# WalkMod_C0.net
KiCad netlist of a schematic drawn in Altium Designer
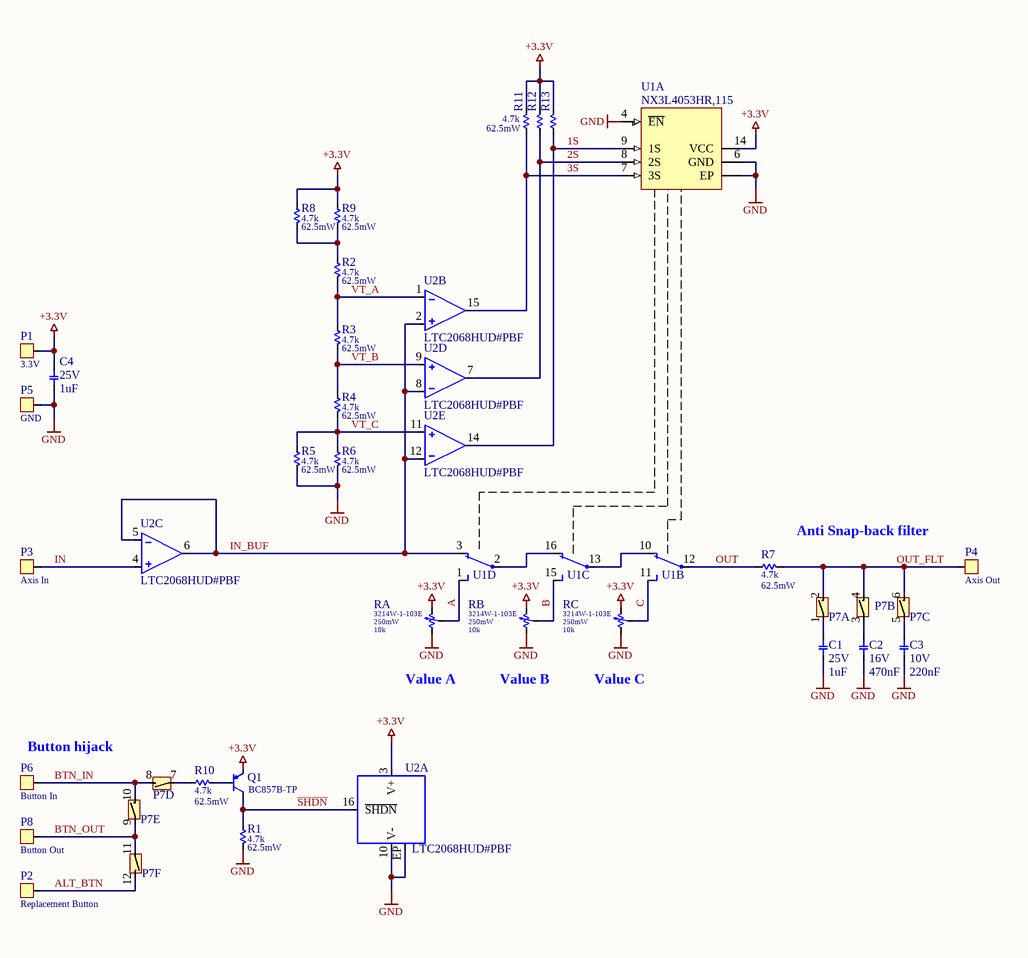
[diagram p0: WalkMod C0.SchDoc]

(export (version "E")
  (design (tool "Eeschema 10.0.6"))
  (components
    (comp (ref "C1")
      (value "1uF")
      (footprint "CX7R0603K")
      (description "1 µF ±10% 25V Ceramic Capacitor X7R 0603 (1608 Metric)")
      (fields (field (name "VALUE2") "25V") (field (name "Comment") "CL10B105KA8NFNC"))
      (libsource (lib "WalkMod") (part "kyocera-C-X7R-0603"))
    )
    (comp (ref "C2")
      (value "470nF")
      (footprint "CX7R0603K")
      (description "0.47 µF ±10% 16V Ceramic Capacitor X7R 0603 (1608 Metric)")
      (fields (field (name "VALUE2") "16V") (field (name "Comment") "CL10B474KO8NFNC"))
      (libsource (lib "WalkMod") (part "kyocera-C-X7R-0603"))
    )
    (comp (ref "C3")
      (value "220nF")
      (footprint "CX7R0603K")
      (description "0.22 µF ±10% 10V Ceramic Capacitor X7R 0603 (1608 Metric)")
      (fields (field (name "VALUE2") "10V") (field (name "Comment") "CC0603KRX7R6BB224"))
      (libsource (lib "WalkMod") (part "kyocera-C-X7R-0603"))
    )
    (comp (ref "C4")
      (value "1uF")
      (footprint "CX7R0603K")
      (description "1 µF ±10% 25V Ceramic Capacitor X7R 0603 (1608 Metric)")
      (fields (field (name "VALUE2") "25V") (field (name "Comment") "CL10B105KA8NFNC"))
      (libsource (lib "WalkMod") (part "kyocera-C-X7R-0603"))
    )
    (comp (ref "P1")
      (value "SMD Pad 1 pin")
      (footprint "PAD_2X1.5_SQUARE")
      (description "Single SMD Pad")
      (fields (field (name "NAME") "3.3V"))
      (libsource (lib "WalkMod") (part "SMD Pad 1 pin"))
    )
    (comp (ref "P2")
      (value "SMD Pad 1 pin")
      (footprint "PAD_2X1.5_SQUARE")
      (description "Single SMD Pad")
      (fields (field (name "NAME") "Replacement Button"))
      (libsource (lib "WalkMod") (part "SMD Pad 1 pin"))
    )
    (comp (ref "P3")
      (value "SMD Pad 1 pin")
      (footprint "PAD_2X1.5_SQUARE")
      (description "Single SMD Pad")
      (fields (field (name "NAME") "Axis In"))
      (libsource (lib "WalkMod") (part "SMD Pad 1 pin"))
    )
    (comp (ref "P4")
      (value "SMD Pad 1 pin")
      (footprint "PAD_2X1.5_SQUARE")
      (description "Single SMD Pad")
      (fields (field (name "NAME") "Axis Out"))
      (libsource (lib "") (part "SMD Pad 1 pin_1"))
    )
    (comp (ref "P5")
      (value "SMD Pad 1 pin")
      (footprint "PAD_2X1.5_SQUARE")
      (description "Single SMD Pad")
      (fields (field (name "NAME") "GND"))
      (libsource (lib "WalkMod") (part "SMD Pad 1 pin"))
    )
    (comp (ref "P6")
      (value "SMD Pad 1 pin")
      (footprint "PAD_2X1.5_SQUARE")
      (description "Single SMD Pad")
      (fields (field (name "NAME") "Button In"))
      (libsource (lib "WalkMod") (part "SMD Pad 1 pin"))
    )
    (comp (ref "P7")
      (value "DS05-127-2-06BK-SMT-TR")
      (footprint "CUI-DS05-127-2-06BK-SMT_C")
      (description "Dip Switch SPST 6 Position Surface Mount Slide (Standard) Actuator 25mA 24VDC")
      (libsource (lib "WalkMod") (part "DS05-127-2-06BK-SMT-TR"))
    )
    (comp (ref "P8")
      (value "SMD Pad 1 pin")
      (footprint "PAD_2X1.5_SQUARE")
      (description "Single SMD Pad")
      (fields (field (name "NAME") "Button Out"))
      (libsource (lib "WalkMod") (part "SMD Pad 1 pin"))
    )
    (comp (ref "Q1")
      (value "BC857B-TP")
      (footprint "BC8xx_SOT23-3_C")
      (description "Bipolar (BJT) Transistor PNP 45 V 100 mA 200MHz 310 mW Surface Mount SOT-23")
      (libsource (lib "WalkMod") (part "BC857B-TP"))
    )
    (comp (ref "R1")
      (value "4.7k")
      (footprint "RT0402_C")
      (fields (field (name "VALUE2") "62.5mW") (field (name "Comment") "RG1005P-472-B-T5"))
      (libsource (lib "WalkMod") (part "RT0402DRD0747KL"))
    )
    (comp (ref "R2")
      (value "4.7k")
      (footprint "RT0402_C")
      (fields (field (name "VALUE2") "62.5mW") (field (name "Comment") "RG1005P-472-B-T5"))
      (libsource (lib "WalkMod") (part "RT0402DRD0747KL"))
    )
    (comp (ref "R3")
      (value "4.7k")
      (footprint "RT0402_C")
      (fields (field (name "VALUE2") "62.5mW") (field (name "Comment") "RG1005P-472-B-T5"))
      (libsource (lib "WalkMod") (part "RT0402DRD0747KL"))
    )
    (comp (ref "R4")
      (value "4.7k")
      (footprint "RT0402_C")
      (fields (field (name "VALUE2") "62.5mW") (field (name "Comment") "RG1005P-472-B-T5"))
      (libsource (lib "WalkMod") (part "RT0402DRD0747KL"))
    )
    (comp (ref "R5")
      (value "4.7k")
      (footprint "RT0402_C")
      (fields (field (name "VALUE2") "62.5mW") (field (name "Comment") "RG1005P-472-B-T5"))
      (libsource (lib "WalkMod") (part "RT0402DRD0747KL"))
    )
    (comp (ref "R6")
      (value "4.7k")
      (footprint "RT0402_C")
      (fields (field (name "VALUE2") "62.5mW") (field (name "Comment") "RG1005P-472-B-T5"))
      (libsource (lib "WalkMod") (part "RT0402DRD0747KL"))
    )
    (comp (ref "R7")
      (value "4.7k")
      (footprint "RT0402_C")
      (fields (field (name "VALUE2") "62.5mW") (field (name "Comment") "RG1005P-472-B-T5"))
      (libsource (lib "WalkMod") (part "RT0402DRD0747KL"))
    )
    (comp (ref "R8")
      (value "4.7k")
      (footprint "RT0402_C")
      (fields (field (name "VALUE2") "62.5mW") (field (name "Comment") "RG1005P-472-B-T5"))
      (libsource (lib "WalkMod") (part "RT0402DRD0747KL"))
    )
    (comp (ref "R9")
      (value "4.7k")
      (footprint "RT0402_C")
      (fields (field (name "VALUE2") "62.5mW") (field (name "Comment") "RG1005P-472-B-T5"))
      (libsource (lib "WalkMod") (part "RT0402DRD0747KL"))
    )
    (comp (ref "R10")
      (value "4.7k")
      (footprint "RT0402_C")
      (fields (field (name "VALUE2") "62.5mW") (field (name "Comment") "RG1005P-472-B-T5"))
      (libsource (lib "WalkMod") (part "RT0402DRD0747KL"))
    )
    (comp (ref "R11")
      (value "4.7k")
      (footprint "RT0402_C")
      (fields (field (name "VALUE2") "62.5mW") (field (name "Comment") "RG1005P-472-B-T5"))
      (libsource (lib "WalkMod") (part "RT0402DRD0747KL"))
    )
    (comp (ref "R12")
      (value "RG1005P-472-B-T5")
      (footprint "RT0402_C")
      (libsource (lib "WalkMod") (part "RT0402DRD0747KL"))
    )
    (comp (ref "R13")
      (value "RG1005P-472-B-T5")
      (footprint "RT0402_C")
      (libsource (lib "WalkMod") (part "RT0402DRD0747KL"))
    )
    (comp (ref "RA")
      (value "3214W-1-103E")
      (footprint "BOURNS_3214W_C")
      (description "10 kOhms 0.25W, 1/4W J Lead Surface Mount Trimmer Potentiometer Cermet 5.0 Turn Top Adjustment")
      (fields (field (name "VALUE2") "250mW") (field (name "ALTIUM_VALUE") "10k"))
      (libsource (lib "WalkMod") (part "3214W-1-103E"))
    )
    (comp (ref "RB")
      (value "3214W-1-103E")
      (footprint "BOURNS_3214W_C")
      (description "10 kOhms 0.25W, 1/4W J Lead Surface Mount Trimmer Potentiometer Cermet 5.0 Turn Top Adjustment")
      (fields (field (name "VALUE2") "250mW") (field (name "ALTIUM_VALUE") "10k"))
      (libsource (lib "WalkMod") (part "3214W-1-103E"))
    )
    (comp (ref "RC")
      (value "3214W-1-103E")
      (footprint "BOURNS_3214W_C")
      (description "10 kOhms 0.25W, 1/4W J Lead Surface Mount Trimmer Potentiometer Cermet 5.0 Turn Top Adjustment")
      (fields (field (name "VALUE2") "250mW") (field (name "ALTIUM_VALUE") "10k"))
      (libsource (lib "WalkMod") (part "3214W-1-103E"))
    )
    (comp (ref "U1")
      (value "NX3L4053HR,115")
      (footprint "HXQFN16_SOT1039-2_C")
      (description "3 Circuit IC Switch 2:1 800mOhm 16-HXQFN (3x3)")
      (libsource (lib "") (part "NX3L4053_3"))
    )
    (comp (ref "U2")
      (value "LTC2068HUD#PBF")
      (footprint "QFN16_0.5_C")
      (description "Zero-Drift Amplifier 4 Circuit Rail-to-Rail 16-QFN (3x3)")
      (libsource (lib "WalkMod") (part "LTC2068HUD#PBF"))
    )
  )
  (nets
    (net (code "1") (name "+3.3V") (class "Default")
      (node (ref "C4") (pin "2") (pinfunction "2_2") (pintype "passive"))
      (node (ref "P1") (pin "1") (pinfunction "1_1") (pintype "passive"))
      (node (ref "Q1") (pin "E") (pinfunction "E_E") (pintype "passive"))
      (node (ref "R11") (pin "1") (pinfunction "1_1") (pintype "passive"))
      (node (ref "R12") (pin "1") (pinfunction "1_1") (pintype "passive"))
      (node (ref "R13") (pin "1") (pinfunction "1_1") (pintype "passive"))
      (node (ref "R8") (pin "2") (pinfunction "2_2") (pintype "passive"))
      (node (ref "R9") (pin "2") (pinfunction "2_2") (pintype "passive"))
      (node (ref "RA") (pin "3") (pinfunction "3_3") (pintype "passive"))
      (node (ref "RB") (pin "3") (pinfunction "3_3") (pintype "passive"))
      (node (ref "RC") (pin "3") (pinfunction "3_3") (pintype "passive"))
      (node (ref "U1") (pin "14") (pinfunction "VCC_14") (pintype "power_in"))
      (node (ref "U2") (pin "3") (pinfunction "V+_3") (pintype "passive"))
    )
    (net (code "2") (name "/1S") (class "Default")
      (node (ref "R13") (pin "2") (pinfunction "2_2") (pintype "passive"))
      (node (ref "U1") (pin "9") (pinfunction "1S_9") (pintype "input"))
      (node (ref "U2") (pin "14") (pinfunction "OUTD_14") (pintype "passive"))
    )
    (net (code "3") (name "/2S") (class "Default")
      (node (ref "R12") (pin "2") (pinfunction "2_2") (pintype "passive"))
      (node (ref "U1") (pin "8") (pinfunction "2S_8") (pintype "input"))
      (node (ref "U2") (pin "7") (pinfunction "OUTC_7") (pintype "passive"))
    )
    (net (code "4") (name "/3S") (class "Default")
      (node (ref "R11") (pin "2") (pinfunction "2_2") (pintype "passive"))
      (node (ref "U1") (pin "7") (pinfunction "3S_7") (pintype "input"))
      (node (ref "U2") (pin "15") (pinfunction "OUTA_15") (pintype "passive"))
    )
    (net (code "5") (name "/A") (class "Default")
      (node (ref "RA") (pin "2") (pinfunction "2_2") (pintype "passive"))
      (node (ref "U1") (pin "1") (pinfunction "3Y1_1") (pintype "passive"))
    )
    (net (code "6") (name "/ALT_BTN") (class "Default")
      (node (ref "P2") (pin "1") (pinfunction "1_1") (pintype "passive"))
      (node (ref "P7") (pin "12") (pinfunction "12_12") (pintype "passive"))
    )
    (net (code "7") (name "/B") (class "Default")
      (node (ref "RB") (pin "2") (pinfunction "2_2") (pintype "passive"))
      (node (ref "U1") (pin "15") (pinfunction "2Y1_15") (pintype "passive"))
    )
    (net (code "8") (name "/BTN_IN") (class "Default")
      (node (ref "P6") (pin "1") (pinfunction "1_1") (pintype "passive"))
      (node (ref "P7") (pin "10") (pinfunction "10_10") (pintype "passive"))
      (node (ref "P7") (pin "8") (pinfunction "8_8") (pintype "passive"))
    )
    (net (code "9") (name "/BTN_OUT") (class "Default")
      (node (ref "P7") (pin "11") (pinfunction "11_11") (pintype "passive"))
      (node (ref "P7") (pin "9") (pinfunction "9_9") (pintype "passive"))
      (node (ref "P8") (pin "1") (pinfunction "1_1") (pintype "passive"))
    )
    (net (code "10") (name "/C") (class "Default")
      (node (ref "RC") (pin "2") (pinfunction "2_2") (pintype "passive"))
      (node (ref "U1") (pin "11") (pinfunction "1Y1_11") (pintype "passive"))
    )
    (net (code "11") (name "/IN") (class "Default")
      (node (ref "P3") (pin "1") (pinfunction "1_1") (pintype "passive"))
      (node (ref "U2") (pin "4") (pinfunction "INB+_4") (pintype "passive"))
    )
    (net (code "12") (name "/IN_BUF") (class "Default")
      (node (ref "U1") (pin "3") (pinfunction "3Y0_3") (pintype "passive"))
      (node (ref "U2") (pin "12") (pinfunction "IND-_12") (pintype "passive"))
      (node (ref "U2") (pin "2") (pinfunction "INA+_2") (pintype "passive"))
      (node (ref "U2") (pin "5") (pinfunction "INB-_5") (pintype "passive"))
      (node (ref "U2") (pin "6") (pinfunction "OUTB_6") (pintype "passive"))
      (node (ref "U2") (pin "8") (pinfunction "INC-_8") (pintype "passive"))
    )
    (net (code "13") (name "/OUT") (class "Default")
      (node (ref "R7") (pin "2") (pinfunction "2_2") (pintype "passive"))
      (node (ref "U1") (pin "12") (pinfunction "1Z_12") (pintype "passive"))
    )
    (net (code "14") (name "/OUT_FLT") (class "Default")
      (node (ref "P4") (pin "1") (pinfunction "1_1") (pintype "passive"))
      (node (ref "P7") (pin "2") (pinfunction "2_2") (pintype "passive"))
      (node (ref "P7") (pin "4") (pinfunction "4_4") (pintype "passive"))
      (node (ref "P7") (pin "6") (pinfunction "6_6") (pintype "passive"))
      (node (ref "R7") (pin "1") (pinfunction "1_1") (pintype "passive"))
    )
    (net (code "15") (name "/VT_A") (class "Default")
      (node (ref "R2") (pin "1") (pinfunction "1_1") (pintype "passive"))
      (node (ref "R3") (pin "2") (pinfunction "2_2") (pintype "passive"))
      (node (ref "U2") (pin "1") (pinfunction "INA-_1") (pintype "passive"))
    )
    (net (code "16") (name "/VT_B") (class "Default")
      (node (ref "R3") (pin "1") (pinfunction "1_1") (pintype "passive"))
      (node (ref "R4") (pin "2") (pinfunction "2_2") (pintype "passive"))
      (node (ref "U2") (pin "9") (pinfunction "INC+_9") (pintype "passive"))
    )
    (net (code "17") (name "/VT_C") (class "Default")
      (node (ref "R4") (pin "1") (pinfunction "1_1") (pintype "passive"))
      (node (ref "R5") (pin "2") (pinfunction "2_2") (pintype "passive"))
      (node (ref "R6") (pin "2") (pinfunction "2_2") (pintype "passive"))
      (node (ref "U2") (pin "11") (pinfunction "IND+_11") (pintype "passive"))
    )
    (net (code "18") (name "/~{SHDN}") (class "Default")
      (node (ref "Q1") (pin "C") (pinfunction "C_C") (pintype "passive"))
      (node (ref "R1") (pin "2") (pinfunction "2_2") (pintype "passive"))
      (node (ref "U2") (pin "16") (pinfunction "~{SHDN}_16") (pintype "passive"))
    )
    (net (code "19") (name "GND") (class "Default")
      (node (ref "C1") (pin "1") (pinfunction "1_1") (pintype "passive"))
      (node (ref "C2") (pin "1") (pinfunction "1_1") (pintype "passive"))
      (node (ref "C3") (pin "1") (pinfunction "1_1") (pintype "passive"))
      (node (ref "C4") (pin "1") (pinfunction "1_1") (pintype "passive"))
      (node (ref "P5") (pin "1") (pinfunction "1_1") (pintype "passive"))
      (node (ref "R1") (pin "1") (pinfunction "1_1") (pintype "passive"))
      (node (ref "R5") (pin "1") (pinfunction "1_1") (pintype "passive"))
      (node (ref "R6") (pin "1") (pinfunction "1_1") (pintype "passive"))
      (node (ref "RA") (pin "1") (pinfunction "1_1") (pintype "passive"))
      (node (ref "RB") (pin "1") (pinfunction "1_1") (pintype "passive"))
      (node (ref "RC") (pin "1") (pinfunction "1_1") (pintype "passive"))
      (node (ref "U1") (pin "4") (pinfunction "~{EN}_4") (pintype "input"))
      (node (ref "U1") (pin "6") (pinfunction "GND_6") (pintype "power_in"))
      (node (ref "U1") (pin "EP") (pinfunction "EP_EP") (pintype "power_in"))
      (node (ref "U2") (pin "10") (pinfunction "V-_10") (pintype "passive"))
      (node (ref "U2") (pin "EP") (pinfunction "EP_EP") (pintype "passive"))
    )
    (net (code "20") (name "Net-(C1-Pad2)") (class "Default")
      (node (ref "C1") (pin "2") (pinfunction "2_2") (pintype "passive"))
      (node (ref "P7") (pin "1") (pinfunction "1_1") (pintype "passive"))
    )
    (net (code "21") (name "Net-(C2-Pad2)") (class "Default")
      (node (ref "C2") (pin "2") (pinfunction "2_2") (pintype "passive"))
      (node (ref "P7") (pin "3") (pinfunction "3_3") (pintype "passive"))
    )
    (net (code "22") (name "Net-(C3-Pad2)") (class "Default")
      (node (ref "C3") (pin "2") (pinfunction "2_2") (pintype "passive"))
      (node (ref "P7") (pin "5") (pinfunction "5_5") (pintype "passive"))
    )
    (net (code "23") (name "Net-(P7-Pad7)") (class "Default")
      (node (ref "P7") (pin "7") (pinfunction "7_7") (pintype "passive"))
      (node (ref "R10") (pin "2") (pinfunction "2_2") (pintype "passive"))
    )
    (net (code "24") (name "Net-(Q1-PadB)") (class "Default")
      (node (ref "Q1") (pin "B") (pinfunction "B_B") (pintype "passive"))
      (node (ref "R10") (pin "1") (pinfunction "1_1") (pintype "passive"))
    )
    (net (code "25") (name "Net-(R2-Pad2)") (class "Default")
      (node (ref "R2") (pin "2") (pinfunction "2_2") (pintype "passive"))
      (node (ref "R8") (pin "1") (pinfunction "1_1") (pintype "passive"))
      (node (ref "R9") (pin "1") (pinfunction "1_1") (pintype "passive"))
    )
    (net (code "26") (name "Net-(U1B-1Y0)") (class "Default")
      (node (ref "U1") (pin "10") (pinfunction "1Y0_10") (pintype "passive"))
      (node (ref "U1") (pin "13") (pinfunction "2Z_13") (pintype "passive"))
    )
    (net (code "27") (name "Net-(U1C-2Y0)") (class "Default")
      (node (ref "U1") (pin "16") (pinfunction "2Y0_16") (pintype "passive"))
      (node (ref "U1") (pin "2") (pinfunction "3Z_2") (pintype "passive"))
    )
  )
)
